# TSAL.net
KiCad netlist of a schematic drawn in EAGLE
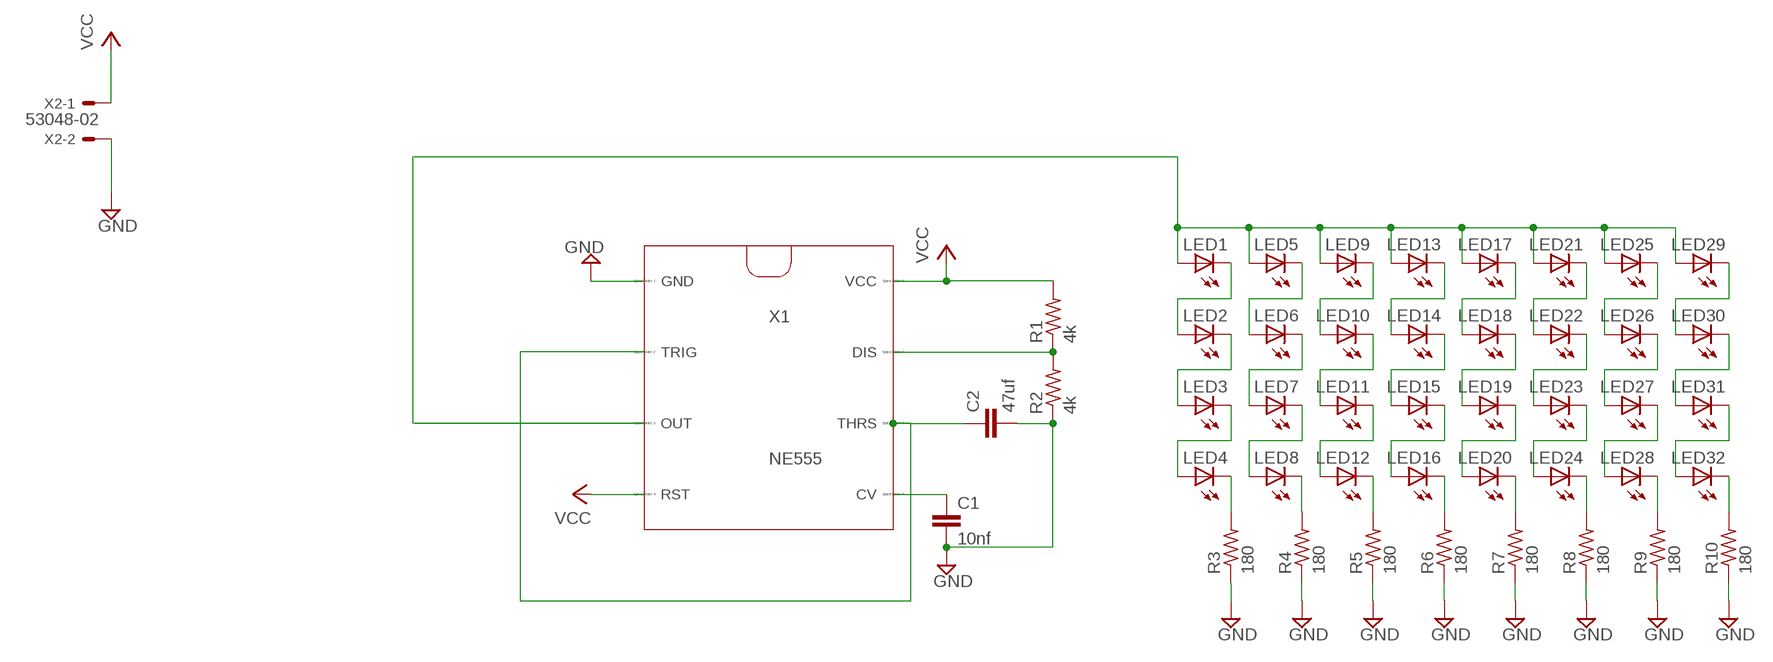
[diagram p0: schematic, sheet 1]

(export (version "E")
  (design (tool "Eeschema 10.0.6"))
  (components
    (comp (ref "C1")
      (value "10nf")
      (footprint "eagle-import:C2.5-3")
      (libsource (lib "eagle-import") (part "C2,5-3"))
    )
    (comp (ref "C2")
      (value "47uf")
      (footprint "eagle-import:C2.5-3")
      (fields (field (name "MPN") "UVZ1C470MDD1TD"))
      (libsource (lib "eagle-import") (part "C2,5-3"))
    )
    (comp (ref "LED1")
      (value "LED5MM")
      (footprint "eagle-import:LED5MM")
      (fields (field (name "MPN") "C503B-RCN-CW0Z0AA1"))
      (libsource (lib "eagle-import") (part "LED5MM"))
    )
    (comp (ref "LED2")
      (value "LED5MM")
      (footprint "eagle-import:LED5MM")
      (fields (field (name "MPN") "C503B-RCN-CW0Z0AA1"))
      (libsource (lib "eagle-import") (part "LED5MM"))
    )
    (comp (ref "LED3")
      (value "LED5MM")
      (footprint "eagle-import:LED5MM")
      (fields (field (name "MPN") "C503B-RCN-CW0Z0AA1"))
      (libsource (lib "eagle-import") (part "LED5MM"))
    )
    (comp (ref "LED4")
      (value "LED5MM")
      (footprint "eagle-import:LED5MM")
      (fields (field (name "MPN") "C503B-RCN-CW0Z0AA1"))
      (libsource (lib "eagle-import") (part "LED5MM"))
    )
    (comp (ref "LED5")
      (value "LED5MM")
      (footprint "eagle-import:LED5MM")
      (fields (field (name "MPN") "C503B-RCN-CW0Z0AA1"))
      (libsource (lib "eagle-import") (part "LED5MM"))
    )
    (comp (ref "LED6")
      (value "LED5MM")
      (footprint "eagle-import:LED5MM")
      (fields (field (name "MPN") "C503B-RCN-CW0Z0AA1"))
      (libsource (lib "eagle-import") (part "LED5MM"))
    )
    (comp (ref "LED7")
      (value "LED5MM")
      (footprint "eagle-import:LED5MM")
      (fields (field (name "MPN") "C503B-RCN-CW0Z0AA1"))
      (libsource (lib "eagle-import") (part "LED5MM"))
    )
    (comp (ref "LED8")
      (value "LED5MM")
      (footprint "eagle-import:LED5MM")
      (fields (field (name "MPN") "C503B-RCN-CW0Z0AA1"))
      (libsource (lib "eagle-import") (part "LED5MM"))
    )
    (comp (ref "LED9")
      (value "LED5MM")
      (footprint "eagle-import:LED5MM")
      (fields (field (name "MPN") "C503B-RCN-CW0Z0AA1"))
      (libsource (lib "eagle-import") (part "LED5MM"))
    )
    (comp (ref "LED10")
      (value "LED5MM")
      (footprint "eagle-import:LED5MM")
      (fields (field (name "MPN") "C503B-RCN-CW0Z0AA1"))
      (libsource (lib "eagle-import") (part "LED5MM"))
    )
    (comp (ref "LED11")
      (value "LED5MM")
      (footprint "eagle-import:LED5MM")
      (fields (field (name "MPN") "C503B-RCN-CW0Z0AA1"))
      (libsource (lib "eagle-import") (part "LED5MM"))
    )
    (comp (ref "LED12")
      (value "LED5MM")
      (footprint "eagle-import:LED5MM")
      (fields (field (name "MPN") "C503B-RCN-CW0Z0AA1"))
      (libsource (lib "eagle-import") (part "LED5MM"))
    )
    (comp (ref "LED13")
      (value "LED5MM")
      (footprint "eagle-import:LED5MM")
      (fields (field (name "MPN") "C503B-RCN-CW0Z0AA1"))
      (libsource (lib "eagle-import") (part "LED5MM"))
    )
    (comp (ref "LED14")
      (value "LED5MM")
      (footprint "eagle-import:LED5MM")
      (fields (field (name "MPN") "C503B-RCN-CW0Z0AA1"))
      (libsource (lib "eagle-import") (part "LED5MM"))
    )
    (comp (ref "LED15")
      (value "LED5MM")
      (footprint "eagle-import:LED5MM")
      (fields (field (name "MPN") "C503B-RCN-CW0Z0AA1"))
      (libsource (lib "eagle-import") (part "LED5MM"))
    )
    (comp (ref "LED16")
      (value "LED5MM")
      (footprint "eagle-import:LED5MM")
      (fields (field (name "MPN") "C503B-RCN-CW0Z0AA1"))
      (libsource (lib "eagle-import") (part "LED5MM"))
    )
    (comp (ref "LED17")
      (value "LED5MM")
      (footprint "eagle-import:LED5MM")
      (fields (field (name "MPN") "C503B-RCN-CW0Z0AA1"))
      (libsource (lib "eagle-import") (part "LED5MM"))
    )
    (comp (ref "LED18")
      (value "LED5MM")
      (footprint "eagle-import:LED5MM")
      (fields (field (name "MPN") "C503B-RCN-CW0Z0AA1"))
      (libsource (lib "eagle-import") (part "LED5MM"))
    )
    (comp (ref "LED19")
      (value "LED5MM")
      (footprint "eagle-import:LED5MM")
      (fields (field (name "MPN") "C503B-RCN-CW0Z0AA1"))
      (libsource (lib "eagle-import") (part "LED5MM"))
    )
    (comp (ref "LED20")
      (value "LED5MM")
      (footprint "eagle-import:LED5MM")
      (fields (field (name "MPN") "C503B-RCN-CW0Z0AA1"))
      (libsource (lib "eagle-import") (part "LED5MM"))
    )
    (comp (ref "LED21")
      (value "LED5MM")
      (footprint "eagle-import:LED5MM")
      (fields (field (name "MPN") "C503B-RCN-CW0Z0AA1"))
      (libsource (lib "eagle-import") (part "LED5MM"))
    )
    (comp (ref "LED22")
      (value "LED5MM")
      (footprint "eagle-import:LED5MM")
      (fields (field (name "MPN") "C503B-RCN-CW0Z0AA1"))
      (libsource (lib "eagle-import") (part "LED5MM"))
    )
    (comp (ref "LED23")
      (value "LED5MM")
      (footprint "eagle-import:LED5MM")
      (fields (field (name "MPN") "C503B-RCN-CW0Z0AA1"))
      (libsource (lib "eagle-import") (part "LED5MM"))
    )
    (comp (ref "LED24")
      (value "LED5MM")
      (footprint "eagle-import:LED5MM")
      (fields (field (name "MPN") "C503B-RCN-CW0Z0AA1"))
      (libsource (lib "eagle-import") (part "LED5MM"))
    )
    (comp (ref "LED25")
      (value "LED5MM")
      (footprint "eagle-import:LED5MM")
      (fields (field (name "MPN") "C503B-RCN-CW0Z0AA1"))
      (libsource (lib "eagle-import") (part "LED5MM"))
    )
    (comp (ref "LED26")
      (value "LED5MM")
      (footprint "eagle-import:LED5MM")
      (fields (field (name "MPN") "C503B-RCN-CW0Z0AA1"))
      (libsource (lib "eagle-import") (part "LED5MM"))
    )
    (comp (ref "LED27")
      (value "LED5MM")
      (footprint "eagle-import:LED5MM")
      (fields (field (name "MPN") "C503B-RCN-CW0Z0AA1"))
      (libsource (lib "eagle-import") (part "LED5MM"))
    )
    (comp (ref "LED28")
      (value "LED5MM")
      (footprint "eagle-import:LED5MM")
      (fields (field (name "MPN") "C503B-RCN-CW0Z0AA1"))
      (libsource (lib "eagle-import") (part "LED5MM"))
    )
    (comp (ref "LED29")
      (value "LED5MM")
      (footprint "eagle-import:LED5MM")
      (fields (field (name "MPN") "C503B-RCN-CW0Z0AA1"))
      (libsource (lib "eagle-import") (part "LED5MM"))
    )
    (comp (ref "LED30")
      (value "LED5MM")
      (footprint "eagle-import:LED5MM")
      (fields (field (name "MPN") "C503B-RCN-CW0Z0AA1"))
      (libsource (lib "eagle-import") (part "LED5MM"))
    )
    (comp (ref "LED31")
      (value "LED5MM")
      (footprint "eagle-import:LED5MM")
      (fields (field (name "MPN") "C503B-RCN-CW0Z0AA1"))
      (libsource (lib "eagle-import") (part "LED5MM"))
    )
    (comp (ref "LED32")
      (value "LED5MM")
      (footprint "eagle-import:LED5MM")
      (fields (field (name "MPN") "C503B-RCN-CW0Z0AA1"))
      (libsource (lib "eagle-import") (part "LED5MM"))
    )
    (comp (ref "R1")
      (value "4k")
      (footprint "eagle-import:0207_10")
      (fields (field (name "MF") "FARNELL") (field (name "MPN") "MCF 0.25W 4K7"))
      (libsource (lib "eagle-import") (part "resistor_348_R-US_0207/10"))
    )
    (comp (ref "R2")
      (value "4k")
      (footprint "eagle-import:0207_10")
      (fields (field (name "MF") "FARNELL") (field (name "MPN") "MCF 0.25W 4K7"))
      (libsource (lib "eagle-import") (part "resistor_348_R-US_0207/10"))
    )
    (comp (ref "R3")
      (value "180")
      (footprint "eagle-import:0207_10")
      (fields (field (name "MF") "FARNELL") (field (name "MPN") "MCF 0.25W 180R"))
      (libsource (lib "eagle-import") (part "R-US_0207/10"))
    )
    (comp (ref "R4")
      (value "180")
      (footprint "eagle-import:0207_10")
      (fields (field (name "MF") "FARNELL") (field (name "MPN") "MCF 0.25W 180R"))
      (libsource (lib "eagle-import") (part "R-US_0207/10"))
    )
    (comp (ref "R5")
      (value "180")
      (footprint "eagle-import:0207_10")
      (fields (field (name "MF") "FARNELL") (field (name "MPN") "MCF 0.25W 180R"))
      (libsource (lib "eagle-import") (part "R-US_0207/10"))
    )
    (comp (ref "R6")
      (value "180")
      (footprint "eagle-import:0207_10")
      (fields (field (name "MF") "FARNELL") (field (name "MPN") "MCF 0.25W 180R"))
      (libsource (lib "eagle-import") (part "R-US_0207/10"))
    )
    (comp (ref "R7")
      (value "180")
      (footprint "eagle-import:0207_10")
      (fields (field (name "MF") "FARNELL") (field (name "MPN") "MCF 0.25W 180R"))
      (libsource (lib "eagle-import") (part "R-US_0207/10"))
    )
    (comp (ref "R8")
      (value "180")
      (footprint "eagle-import:0207_10")
      (fields (field (name "MF") "FARNELL") (field (name "MPN") "MCF 0.25W 180R"))
      (libsource (lib "eagle-import") (part "R-US_0207/10"))
    )
    (comp (ref "R9")
      (value "180")
      (footprint "eagle-import:0207_10")
      (fields (field (name "MF") "FARNELL") (field (name "MPN") "MCF 0.25W 180R"))
      (libsource (lib "eagle-import") (part "R-US_0207/10"))
    )
    (comp (ref "R10")
      (value "180")
      (footprint "eagle-import:0207_10")
      (fields (field (name "MF") "FARNELL") (field (name "MPN") "MCF 0.25W 180R"))
      (libsource (lib "eagle-import") (part "R-US_0207/10"))
    )
    (comp (ref "X1")
      (value "NE555")
      (footprint "eagle-import:SOIC8")
      (fields (field (name "MF") "TEXAS INSTRUMENTS") (field (name "MPN") "NE555P"))
      (libsource (lib "eagle-import") (part "NE555"))
    )
    (comp (ref "X2")
      (value "53048-02")
      (footprint "eagle-import:53048-02")
      (fields (field (name "MF") "MOLEX") (field (name "MPN") "53048-0210"))
      (libsource (lib "eagle-import") (part "53?-02048"))
    )
  )
  (nets
    (net (code "1") (name "GND") (class "Default")
      (node (ref "C1") (pin "2") (pinfunction "2_2") (pintype "passive"))
      (node (ref "C2") (pin "2") (pinfunction "2_2") (pintype "passive"))
      (node (ref "R10") (pin "1") (pinfunction "1_1") (pintype "passive"))
      (node (ref "R2") (pin "1") (pinfunction "1_1") (pintype "passive"))
      (node (ref "R3") (pin "1") (pinfunction "1_1") (pintype "passive"))
      (node (ref "R4") (pin "1") (pinfunction "1_1") (pintype "passive"))
      (node (ref "R5") (pin "1") (pinfunction "1_1") (pintype "passive"))
      (node (ref "R6") (pin "1") (pinfunction "1_1") (pintype "passive"))
      (node (ref "R7") (pin "1") (pinfunction "1_1") (pintype "passive"))
      (node (ref "R8") (pin "1") (pinfunction "1_1") (pintype "passive"))
      (node (ref "R9") (pin "1") (pinfunction "1_1") (pintype "passive"))
      (node (ref "X1") (pin "1") (pinfunction "GND_1") (pintype "passive"))
      (node (ref "X2") (pin "2") (pinfunction "S_2") (pintype "passive"))
    )
    (net (code "2") (name "Net-(LED1-C)") (class "Default")
      (node (ref "LED1") (pin "K") (pinfunction "C_K") (pintype "passive"))
      (node (ref "LED2") (pin "A") (pinfunction "A_A") (pintype "passive"))
    )
    (net (code "3") (name "Net-(LED2-C)") (class "Default")
      (node (ref "LED2") (pin "K") (pinfunction "C_K") (pintype "passive"))
      (node (ref "LED3") (pin "A") (pinfunction "A_A") (pintype "passive"))
    )
    (net (code "4") (name "Net-(LED3-C)") (class "Default")
      (node (ref "LED3") (pin "K") (pinfunction "C_K") (pintype "passive"))
      (node (ref "LED4") (pin "A") (pinfunction "A_A") (pintype "passive"))
    )
    (net (code "5") (name "Net-(LED4-C)") (class "Default")
      (node (ref "LED4") (pin "K") (pinfunction "C_K") (pintype "passive"))
      (node (ref "R3") (pin "2") (pinfunction "2_2") (pintype "passive"))
    )
    (net (code "6") (name "Net-(LED5-C)") (class "Default")
      (node (ref "LED5") (pin "K") (pinfunction "C_K") (pintype "passive"))
      (node (ref "LED6") (pin "A") (pinfunction "A_A") (pintype "passive"))
    )
    (net (code "7") (name "Net-(LED6-C)") (class "Default")
      (node (ref "LED6") (pin "K") (pinfunction "C_K") (pintype "passive"))
      (node (ref "LED7") (pin "A") (pinfunction "A_A") (pintype "passive"))
    )
    (net (code "8") (name "Net-(LED7-C)") (class "Default")
      (node (ref "LED7") (pin "K") (pinfunction "C_K") (pintype "passive"))
      (node (ref "LED8") (pin "A") (pinfunction "A_A") (pintype "passive"))
    )
    (net (code "9") (name "Net-(LED8-C)") (class "Default")
      (node (ref "LED8") (pin "K") (pinfunction "C_K") (pintype "passive"))
      (node (ref "R4") (pin "2") (pinfunction "2_2") (pintype "passive"))
    )
    (net (code "10") (name "Net-(LED9-C)") (class "Default")
      (node (ref "LED10") (pin "A") (pinfunction "A_A") (pintype "passive"))
      (node (ref "LED9") (pin "K") (pinfunction "C_K") (pintype "passive"))
    )
    (net (code "11") (name "Net-(LED10-C)") (class "Default")
      (node (ref "LED10") (pin "K") (pinfunction "C_K") (pintype "passive"))
      (node (ref "LED11") (pin "A") (pinfunction "A_A") (pintype "passive"))
    )
    (net (code "12") (name "Net-(LED11-C)") (class "Default")
      (node (ref "LED11") (pin "K") (pinfunction "C_K") (pintype "passive"))
      (node (ref "LED12") (pin "A") (pinfunction "A_A") (pintype "passive"))
    )
    (net (code "13") (name "Net-(LED12-C)") (class "Default")
      (node (ref "LED12") (pin "K") (pinfunction "C_K") (pintype "passive"))
      (node (ref "R5") (pin "2") (pinfunction "2_2") (pintype "passive"))
    )
    (net (code "14") (name "Net-(LED13-C)") (class "Default")
      (node (ref "LED13") (pin "K") (pinfunction "C_K") (pintype "passive"))
      (node (ref "LED14") (pin "A") (pinfunction "A_A") (pintype "passive"))
    )
    (net (code "15") (name "Net-(LED14-C)") (class "Default")
      (node (ref "LED14") (pin "K") (pinfunction "C_K") (pintype "passive"))
      (node (ref "LED15") (pin "A") (pinfunction "A_A") (pintype "passive"))
    )
    (net (code "16") (name "Net-(LED15-C)") (class "Default")
      (node (ref "LED15") (pin "K") (pinfunction "C_K") (pintype "passive"))
      (node (ref "LED16") (pin "A") (pinfunction "A_A") (pintype "passive"))
    )
    (net (code "17") (name "Net-(LED16-C)") (class "Default")
      (node (ref "LED16") (pin "K") (pinfunction "C_K") (pintype "passive"))
      (node (ref "R6") (pin "2") (pinfunction "2_2") (pintype "passive"))
    )
    (net (code "18") (name "Net-(LED17-C)") (class "Default")
      (node (ref "LED17") (pin "K") (pinfunction "C_K") (pintype "passive"))
      (node (ref "LED18") (pin "A") (pinfunction "A_A") (pintype "passive"))
    )
    (net (code "19") (name "Net-(LED18-C)") (class "Default")
      (node (ref "LED18") (pin "K") (pinfunction "C_K") (pintype "passive"))
      (node (ref "LED19") (pin "A") (pinfunction "A_A") (pintype "passive"))
    )
    (net (code "20") (name "Net-(LED19-C)") (class "Default")
      (node (ref "LED19") (pin "K") (pinfunction "C_K") (pintype "passive"))
      (node (ref "LED20") (pin "A") (pinfunction "A_A") (pintype "passive"))
    )
    (net (code "21") (name "Net-(LED20-C)") (class "Default")
      (node (ref "LED20") (pin "K") (pinfunction "C_K") (pintype "passive"))
      (node (ref "R7") (pin "2") (pinfunction "2_2") (pintype "passive"))
    )
    (net (code "22") (name "Net-(LED21-C)") (class "Default")
      (node (ref "LED21") (pin "K") (pinfunction "C_K") (pintype "passive"))
      (node (ref "LED22") (pin "A") (pinfunction "A_A") (pintype "passive"))
    )
    (net (code "23") (name "Net-(LED22-C)") (class "Default")
      (node (ref "LED22") (pin "K") (pinfunction "C_K") (pintype "passive"))
      (node (ref "LED23") (pin "A") (pinfunction "A_A") (pintype "passive"))
    )
    (net (code "24") (name "Net-(LED23-C)") (class "Default")
      (node (ref "LED23") (pin "K") (pinfunction "C_K") (pintype "passive"))
      (node (ref "LED24") (pin "A") (pinfunction "A_A") (pintype "passive"))
    )
    (net (code "25") (name "Net-(LED24-C)") (class "Default")
      (node (ref "LED24") (pin "K") (pinfunction "C_K") (pintype "passive"))
      (node (ref "R8") (pin "2") (pinfunction "2_2") (pintype "passive"))
    )
    (net (code "26") (name "Net-(LED25-C)") (class "Default")
      (node (ref "LED25") (pin "K") (pinfunction "C_K") (pintype "passive"))
      (node (ref "LED26") (pin "A") (pinfunction "A_A") (pintype "passive"))
    )
    (net (code "27") (name "Net-(LED26-C)") (class "Default")
      (node (ref "LED26") (pin "K") (pinfunction "C_K") (pintype "passive"))
      (node (ref "LED27") (pin "A") (pinfunction "A_A") (pintype "passive"))
    )
    (net (code "28") (name "Net-(LED27-C)") (class "Default")
      (node (ref "LED27") (pin "K") (pinfunction "C_K") (pintype "passive"))
      (node (ref "LED28") (pin "A") (pinfunction "A_A") (pintype "passive"))
    )
    (net (code "29") (name "Net-(LED28-C)") (class "Default")
      (node (ref "LED28") (pin "K") (pinfunction "C_K") (pintype "passive"))
      (node (ref "R9") (pin "2") (pinfunction "2_2") (pintype "passive"))
    )
    (net (code "30") (name "Net-(LED29-C)") (class "Default")
      (node (ref "LED29") (pin "K") (pinfunction "C_K") (pintype "passive"))
      (node (ref "LED30") (pin "A") (pinfunction "A_A") (pintype "passive"))
    )
    (net (code "31") (name "Net-(LED30-C)") (class "Default")
      (node (ref "LED30") (pin "K") (pinfunction "C_K") (pintype "passive"))
      (node (ref "LED31") (pin "A") (pinfunction "A_A") (pintype "passive"))
    )
    (net (code "32") (name "Net-(LED31-C)") (class "Default")
      (node (ref "LED31") (pin "K") (pinfunction "C_K") (pintype "passive"))
      (node (ref "LED32") (pin "A") (pinfunction "A_A") (pintype "passive"))
    )
    (net (code "33") (name "Net-(LED32-C)") (class "Default")
      (node (ref "LED32") (pin "K") (pinfunction "C_K") (pintype "passive"))
      (node (ref "R10") (pin "2") (pinfunction "2_2") (pintype "passive"))
    )
    (net (code "34") (name "Net-(X1-CV)") (class "Default")
      (node (ref "C1") (pin "1") (pinfunction "1_1") (pintype "passive"))
      (node (ref "X1") (pin "5") (pinfunction "CV_5") (pintype "passive"))
    )
    (net (code "35") (name "Net-(X1-DIS)") (class "Default")
      (node (ref "R1") (pin "1") (pinfunction "1_1") (pintype "passive"))
      (node (ref "R2") (pin "2") (pinfunction "2_2") (pintype "passive"))
      (node (ref "X1") (pin "7") (pinfunction "DIS_7") (pintype "passive"))
    )
    (net (code "36") (name "Net-(X1-OUT)") (class "Default")
      (node (ref "LED1") (pin "A") (pinfunction "A_A") (pintype "passive"))
      (node (ref "LED13") (pin "A") (pinfunction "A_A") (pintype "passive"))
      (node (ref "LED17") (pin "A") (pinfunction "A_A") (pintype "passive"))
      (node (ref "LED21") (pin "A") (pinfunction "A_A") (pintype "passive"))
      (node (ref "LED25") (pin "A") (pinfunction "A_A") (pintype "passive"))
      (node (ref "LED29") (pin "A") (pinfunction "A_A") (pintype "passive"))
      (node (ref "LED5") (pin "A") (pinfunction "A_A") (pintype "passive"))
      (node (ref "LED9") (pin "A") (pinfunction "A_A") (pintype "passive"))
      (node (ref "X1") (pin "3") (pinfunction "OUT_3") (pintype "passive"))
    )
    (net (code "37") (name "Net-(X1-THRS)") (class "Default")
      (node (ref "C2") (pin "1") (pinfunction "1_1") (pintype "passive"))
      (node (ref "X1") (pin "2") (pinfunction "TRIG_2") (pintype "passive"))
      (node (ref "X1") (pin "6") (pinfunction "THRS_6") (pintype "passive"))
    )
    (net (code "38") (name "VCC") (class "Default")
      (node (ref "R1") (pin "2") (pinfunction "2_2") (pintype "passive"))
      (node (ref "X1") (pin "4") (pinfunction "RST_4") (pintype "passive"))
      (node (ref "X1") (pin "8") (pinfunction "VCC_8") (pintype "passive"))
      (node (ref "X2") (pin "1") (pinfunction "S_1") (pintype "passive"))
    )
  )
)
